# FPGA_IO.net
KiCad netlist of a schematic drawn in Altium Designer
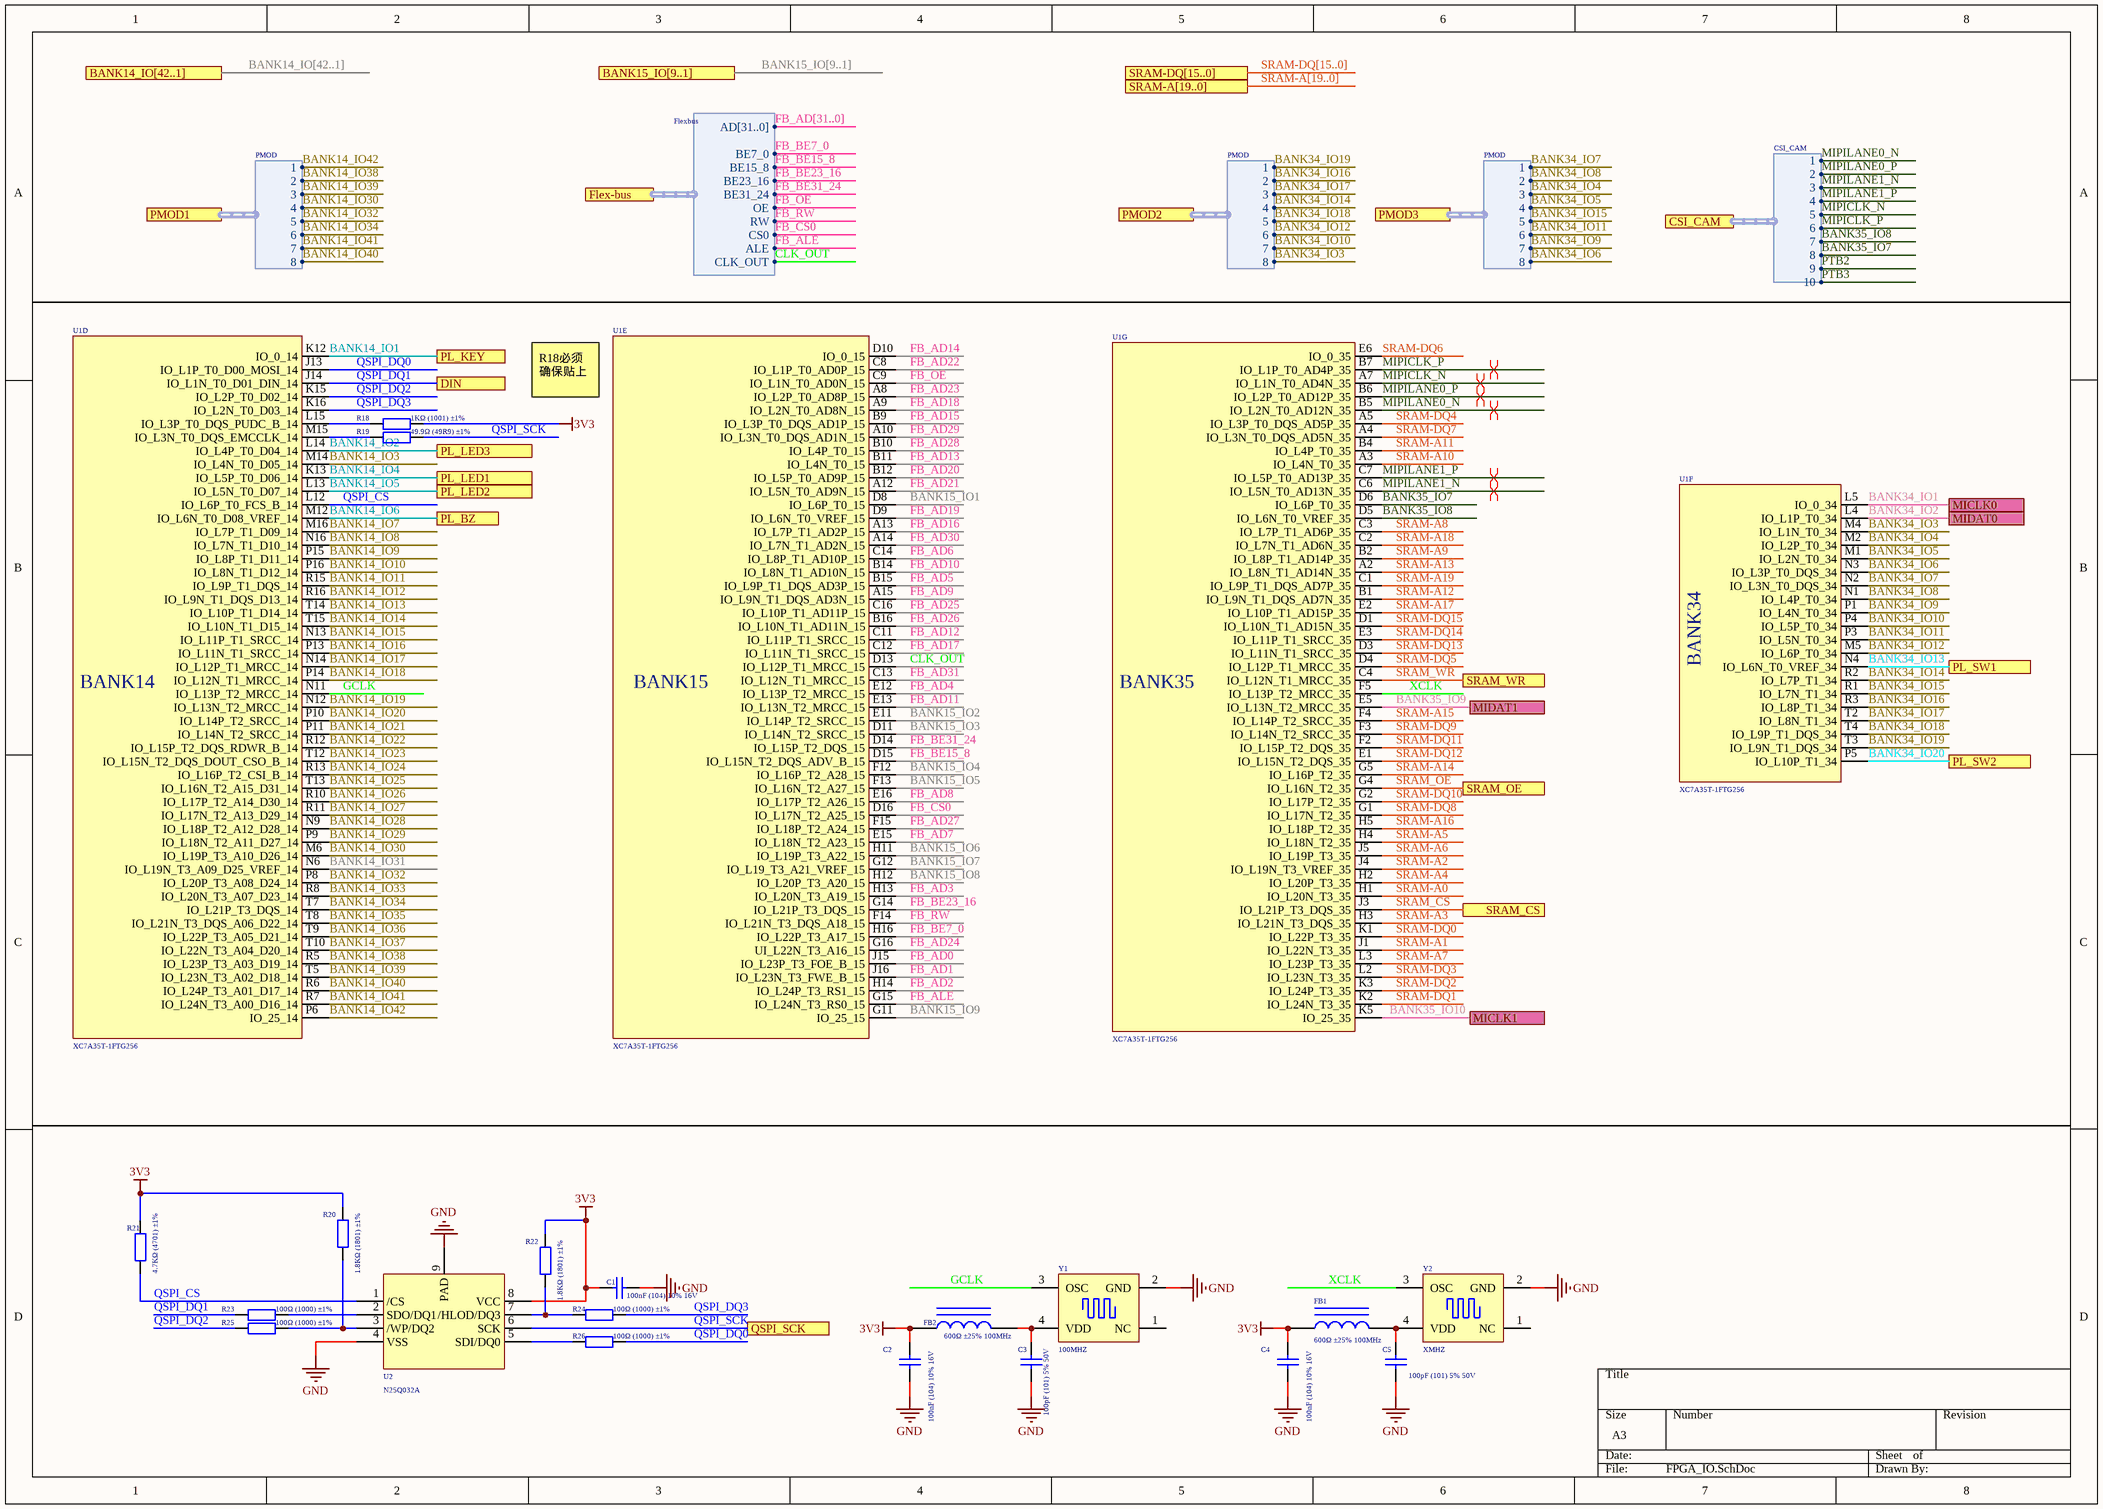
[diagram p0: FPGA_IO.SchDoc]

(export (version "E")
  (design (tool "Eeschema 10.0.6"))
  (components
    (comp (ref "C1")
      (value "100nF (104) 10% 16V")
      (footprint "0402_C")
      (description "贴片电容")
      (libsource (lib "Cap") (part "0402 100nF (104) 10% 16V"))
    )
    (comp (ref "C2")
      (value "100nF (104) 10% 16V")
      (footprint "0402_C")
      (description "贴片电容")
      (libsource (lib "Cap") (part "0402 100nF (104) 10% 16V"))
    )
    (comp (ref "C3")
      (value "100pF (101) 5% 50V")
      (footprint "0402_C")
      (description "贴片电容")
      (libsource (lib "Cap") (part "0402 100pF (101) 5% 50V"))
    )
    (comp (ref "C4")
      (value "100nF (104) 10% 16V")
      (footprint "0402_C")
      (description "贴片电容")
      (libsource (lib "Cap") (part "0402 100nF (104) 10% 16V"))
    )
    (comp (ref "C5")
      (value "100pF (101) 5% 50V")
      (footprint "0402_C")
      (description "贴片电容")
      (libsource (lib "Cap") (part "0402 100pF (101) 5% 50V"))
    )
    (comp (ref "FB1")
      (value "600Ω ±25% 100MHz")
      (footprint "0805_L")
      (description "贴片磁珠")
      (libsource (lib "IUD") (part "0805 600Ω 25% 100MHz"))
    )
    (comp (ref "FB2")
      (value "600Ω ±25% 100MHz")
      (footprint "0805_L")
      (description "贴片磁珠")
      (libsource (lib "IUD") (part "0805 600Ω 25% 100MHz"))
    )
    (comp (ref "R18")
      (value "1KΩ (1001) ±1%")
      (footprint "0402_R")
      (description "贴片电阻")
      (libsource (lib "RES") (part "0402 1KΩ (1001) 1%"))
    )
    (comp (ref "R19")
      (value "49.9Ω (49R9) ±1%")
      (footprint "0402_R")
      (description "贴片电阻")
      (libsource (lib "RES") (part "0402 49.9Ω (49R9) 1%"))
    )
    (comp (ref "R20")
      (value "1.8KΩ (1801) ±1%")
      (footprint "0603_R")
      (description "贴片电阻")
      (libsource (lib "RES") (part "0603 1.8KΩ (1801) 1%"))
    )
    (comp (ref "R21")
      (value "4.7KΩ (4701) ±1%")
      (footprint "0402_R")
      (description "贴片电阻")
      (libsource (lib "RES") (part "0402 4.7KΩ (4701) 1%"))
    )
    (comp (ref "R22")
      (value "1.8KΩ (1801) ±1%")
      (footprint "0603_R")
      (description "贴片电阻")
      (libsource (lib "RES") (part "0603 1.8KΩ (1801) 1%"))
    )
    (comp (ref "R23")
      (value "100Ω (1000) ±1%")
      (footprint "0402_R")
      (description "贴片电阻")
      (libsource (lib "RES") (part "0402 100Ω (1000) 1%"))
    )
    (comp (ref "R24")
      (value "100Ω (1000) ±1%")
      (footprint "0402_R")
      (description "贴片电阻")
      (libsource (lib "RES") (part "0402 100Ω (1000) 1%"))
    )
    (comp (ref "R25")
      (value "100Ω (1000) ±1%")
      (footprint "0402_R")
      (description "贴片电阻")
      (libsource (lib "RES") (part "0402 100Ω (1000) 1%"))
    )
    (comp (ref "R26")
      (value "100Ω (1000) ±1%")
      (footprint "0402_R")
      (description "贴片电阻")
      (libsource (lib "RES") (part "0402 100Ω (1000) 1%"))
    )
    (comp (ref "U1")
      (value "XC7A35T-1FTG256")
      (footprint "BGA100P9X9-81A")
      (libsource (lib "Schlib") (part "XC7A35T-1FTG256"))
    )
    (comp (ref "U2")
      (value "N25Q032A")
      (footprint "QFN127P500X600X100_HS-9N")
      (libsource (lib "2号库") (part "N25Q032A"))
    )
    (comp (ref "Y1") (value "100MHZ") (footprint "XTAL7_3225") (libsource (lib "K60-V4.0") (part "XTAL1")))
    (comp (ref "Y2") (value "XMHZ") (footprint "XTAL7_3225") (libsource (lib "K60-V4.0") (part "XTAL1")))
  )
  (nets
    (net (code "4") (name "/BANK14_IO1") (class "Default")
      (node (ref "U1") (pin "K12") (pinfunction "IO_0_14_K12") (pintype "passive"))
    )
    (net (code "5") (name "/BANK14_IO2") (class "Default")
      (node (ref "U1") (pin "L14") (pinfunction "IO_L4P_T0_D04_14_L14") (pintype "passive"))
    )
    (net (code "6") (name "/BANK14_IO3") (class "Default")
      (node (ref "U1") (pin "M14") (pinfunction "IO_L4N_T0_D05_14_M14") (pintype "passive"))
    )
    (net (code "7") (name "/BANK14_IO4") (class "Default")
      (node (ref "U1") (pin "K13") (pinfunction "IO_L5P_T0_D06_14_K13") (pintype "passive"))
    )
    (net (code "8") (name "/BANK14_IO5") (class "Default")
      (node (ref "U1") (pin "L13") (pinfunction "IO_L5N_T0_D07_14_L13") (pintype "passive"))
    )
    (net (code "9") (name "/BANK14_IO6") (class "Default")
      (node (ref "U1") (pin "M12") (pinfunction "IO_L6N_T0_D08_VREF_14_M12") (pintype "passive"))
    )
    (net (code "10") (name "/BANK14_IO7") (class "Default")
      (node (ref "U1") (pin "M16") (pinfunction "IO_L7P_T1_D09_14_M16") (pintype "passive"))
    )
    (net (code "11") (name "/BANK14_IO8") (class "Default")
      (node (ref "U1") (pin "N16") (pinfunction "IO_L7N_T1_D10_14_N16") (pintype "passive"))
    )
    (net (code "12") (name "/BANK14_IO9") (class "Default")
      (node (ref "U1") (pin "P15") (pinfunction "IO_L8P_T1_D11_14_P15") (pintype "passive"))
    )
    (net (code "13") (name "/BANK14_IO10") (class "Default")
      (node (ref "U1") (pin "P16") (pinfunction "IO_L8N_T1_D12_14_P16") (pintype "passive"))
    )
    (net (code "14") (name "/BANK14_IO11") (class "Default")
      (node (ref "U1") (pin "R15") (pinfunction "IO_L9P_T1_DQS_14_R15") (pintype "passive"))
    )
    (net (code "15") (name "/BANK14_IO12") (class "Default")
      (node (ref "U1") (pin "R16") (pinfunction "IO_L9N_T1_DQS_D13_14_R16") (pintype "passive"))
    )
    (net (code "16") (name "/BANK14_IO13") (class "Default")
      (node (ref "U1") (pin "T14") (pinfunction "IO_L10P_T1_D14_14_T14") (pintype "passive"))
    )
    (net (code "17") (name "/BANK14_IO14") (class "Default")
      (node (ref "U1") (pin "T15") (pinfunction "IO_L10N_T1_D15_14_T15") (pintype "passive"))
    )
    (net (code "18") (name "/BANK14_IO15") (class "Default")
      (node (ref "U1") (pin "N13") (pinfunction "IO_L11P_T1_SRCC_14_N13") (pintype "passive"))
    )
    (net (code "19") (name "/BANK14_IO16") (class "Default")
      (node (ref "U1") (pin "P13") (pinfunction "IO_L11N_T1_SRCC_14_P13") (pintype "passive"))
    )
    (net (code "20") (name "/BANK14_IO17") (class "Default")
      (node (ref "U1") (pin "N14") (pinfunction "IO_L12P_T1_MRCC_14_N14") (pintype "passive"))
    )
    (net (code "21") (name "/BANK14_IO18") (class "Default")
      (node (ref "U1") (pin "P14") (pinfunction "IO_L12N_T1_MRCC_14_P14") (pintype "passive"))
    )
    (net (code "22") (name "/BANK14_IO19") (class "Default")
      (node (ref "U1") (pin "N12") (pinfunction "IO_L13N_T2_MRCC_14_N12") (pintype "passive"))
    )
    (net (code "23") (name "/BANK14_IO20") (class "Default")
      (node (ref "U1") (pin "P10") (pinfunction "IO_L14P_T2_SRCC_14_P10") (pintype "passive"))
    )
    (net (code "24") (name "/BANK14_IO21") (class "Default")
      (node (ref "U1") (pin "P11") (pinfunction "IO_L14N_T2_SRCC_14_P11") (pintype "passive"))
    )
    (net (code "25") (name "/BANK14_IO22") (class "Default")
      (node (ref "U1") (pin "R12") (pinfunction "IO_L15P_T2_DQS_RDWR_B_14_R12") (pintype "passive"))
    )
    (net (code "26") (name "/BANK14_IO23") (class "Default")
      (node (ref "U1") (pin "T12") (pinfunction "IO_L15N_T2_DQS_DOUT_CSO_B_14_T12") (pintype "passive"))
    )
    (net (code "27") (name "/BANK14_IO24") (class "Default")
      (node (ref "U1") (pin "R13") (pinfunction "IO_L16P_T2_CSI_B_14_R13") (pintype "passive"))
    )
    (net (code "28") (name "/BANK14_IO25") (class "Default")
      (node (ref "U1") (pin "T13") (pinfunction "IO_L16N_T2_A15_D31_14_T13") (pintype "passive"))
    )
    (net (code "29") (name "/BANK14_IO26") (class "Default")
      (node (ref "U1") (pin "R10") (pinfunction "IO_L17P_T2_A14_D30_14_R10") (pintype "passive"))
    )
    (net (code "30") (name "/BANK14_IO27") (class "Default")
      (node (ref "U1") (pin "R11") (pinfunction "IO_L17N_T2_A13_D29_14_R11") (pintype "passive"))
    )
    (net (code "31") (name "/BANK14_IO28") (class "Default")
      (node (ref "U1") (pin "N9") (pinfunction "IO_L18P_T2_A12_D28_14_N9") (pintype "passive"))
    )
    (net (code "32") (name "/BANK14_IO29") (class "Default")
      (node (ref "U1") (pin "P9") (pinfunction "IO_L18N_T2_A11_D27_14_P9") (pintype "passive"))
    )
    (net (code "33") (name "/BANK14_IO30") (class "Default")
      (node (ref "U1") (pin "M6") (pinfunction "IO_L19P_T3_A10_D26_14_M6") (pintype "passive"))
    )
    (net (code "34") (name "/BANK14_IO31") (class "Default")
      (node (ref "U1") (pin "N6") (pinfunction "IO_L19N_T3_A09_D25_VREF_14_N6") (pintype "passive"))
    )
    (net (code "35") (name "/BANK14_IO32") (class "Default")
      (node (ref "U1") (pin "P8") (pinfunction "IO_L20P_T3_A08_D24_14_P8") (pintype "passive"))
    )
    (net (code "36") (name "/BANK14_IO33") (class "Default")
      (node (ref "U1") (pin "R8") (pinfunction "IO_L20N_T3_A07_D23_14_R8") (pintype "passive"))
    )
    (net (code "37") (name "/BANK14_IO34") (class "Default")
      (node (ref "U1") (pin "T7") (pinfunction "IO_L21P_T3_DQS_14_T7") (pintype "passive"))
    )
    (net (code "38") (name "/BANK14_IO35") (class "Default")
      (node (ref "U1") (pin "T8") (pinfunction "IO_L21N_T3_DQS_A06_D22_14_T8") (pintype "passive"))
    )
    (net (code "39") (name "/BANK14_IO36") (class "Default")
      (node (ref "U1") (pin "T9") (pinfunction "IO_L22P_T3_A05_D21_14_T9") (pintype "passive"))
    )
    (net (code "40") (name "/BANK14_IO37") (class "Default")
      (node (ref "U1") (pin "T10") (pinfunction "IO_L22N_T3_A04_D20_14_T10") (pintype "passive"))
    )
    (net (code "41") (name "/BANK14_IO38") (class "Default")
      (node (ref "U1") (pin "R5") (pinfunction "IO_L23P_T3_A03_D19_14_R5") (pintype "passive"))
    )
    (net (code "42") (name "/BANK14_IO39") (class "Default")
      (node (ref "U1") (pin "T5") (pinfunction "IO_L23N_T3_A02_D18_14_T5") (pintype "passive"))
    )
    (net (code "43") (name "/BANK14_IO40") (class "Default")
      (node (ref "U1") (pin "R6") (pinfunction "IO_L24P_T3_A01_D17_14_R6") (pintype "passive"))
    )
    (net (code "44") (name "/BANK14_IO41") (class "Default")
      (node (ref "U1") (pin "R7") (pinfunction "IO_L24N_T3_A00_D16_14_R7") (pintype "passive"))
    )
    (net (code "45") (name "/BANK14_IO42") (class "Default")
      (node (ref "U1") (pin "P6") (pinfunction "IO_25_14_P6") (pintype "passive"))
    )
    (net (code "47") (name "/BANK15_IO1") (class "Default")
      (node (ref "U1") (pin "D8") (pinfunction "IO_L6P_T0_15_D8") (pintype "passive"))
    )
    (net (code "48") (name "/BANK15_IO2") (class "Default")
      (node (ref "U1") (pin "E11") (pinfunction "IO_L14P_T2_SRCC_15_E11") (pintype "passive"))
    )
    (net (code "49") (name "/BANK15_IO3") (class "Default")
      (node (ref "U1") (pin "D11") (pinfunction "IO_L14N_T2_SRCC_15_D11") (pintype "passive"))
    )
    (net (code "50") (name "/BANK15_IO4") (class "Default")
      (node (ref "U1") (pin "F12") (pinfunction "IO_L16P_T2_A28_15_F12") (pintype "passive"))
    )
    (net (code "51") (name "/BANK15_IO5") (class "Default")
      (node (ref "U1") (pin "F13") (pinfunction "IO_L16N_T2_A27_15_F13") (pintype "passive"))
    )
    (net (code "52") (name "/BANK15_IO6") (class "Default")
      (node (ref "U1") (pin "H11") (pinfunction "IO_L19P_T3_A22_15_H11") (pintype "passive"))
    )
    (net (code "53") (name "/BANK15_IO7") (class "Default")
      (node (ref "U1") (pin "G12") (pinfunction "IO_L19_T3_A21_VREF_15_G12") (pintype "passive"))
    )
    (net (code "54") (name "/BANK15_IO8") (class "Default")
      (node (ref "U1") (pin "H12") (pinfunction "IO_L20P_T3_A20_15_H12") (pintype "passive"))
    )
    (net (code "55") (name "/BANK15_IO9") (class "Default")
      (node (ref "U1") (pin "G11") (pinfunction "IO_25_15_G11") (pintype "passive"))
    )
    (net (code "57") (name "/BANK34_IO1") (class "Default")
      (node (ref "U1") (pin "L5") (pinfunction "IO_0_34_L5") (pintype "passive"))
    )
    (net (code "58") (name "/BANK34_IO2") (class "Default")
      (node (ref "U1") (pin "L4") (pinfunction "IO_L1P_T0_34_L4") (pintype "passive"))
    )
    (net (code "59") (name "/BANK34_IO3") (class "Default")
      (node (ref "U1") (pin "M4") (pinfunction "IO_L1N_T0_34_M4") (pintype "passive"))
    )
    (net (code "60") (name "/BANK34_IO4") (class "Default")
      (node (ref "U1") (pin "M2") (pinfunction "IO_L2P_T0_34_M2") (pintype "passive"))
    )
    (net (code "61") (name "/BANK34_IO5") (class "Default")
      (node (ref "U1") (pin "M1") (pinfunction "IO_L2N_T0_34_M1") (pintype "passive"))
    )
    (net (code "62") (name "/BANK34_IO6") (class "Default")
      (node (ref "U1") (pin "N3") (pinfunction "IO_L3P_T0_DQS_34_N3") (pintype "passive"))
    )
    (net (code "63") (name "/BANK34_IO7") (class "Default")
      (node (ref "U1") (pin "N2") (pinfunction "IO_L3N_T0_DQS_34_N2") (pintype "passive"))
    )
    (net (code "64") (name "/BANK34_IO8") (class "Default")
      (node (ref "U1") (pin "N1") (pinfunction "IO_L4P_T0_34_N1") (pintype "passive"))
    )
    (net (code "65") (name "/BANK34_IO9") (class "Default")
      (node (ref "U1") (pin "P1") (pinfunction "IO_L4N_T0_34_P1") (pintype "passive"))
    )
    (net (code "66") (name "/BANK34_IO10") (class "Default")
      (node (ref "U1") (pin "P4") (pinfunction "IO_L5P_T0_34_P4") (pintype "passive"))
    )
    (net (code "67") (name "/BANK34_IO11") (class "Default")
      (node (ref "U1") (pin "P3") (pinfunction "IO_L5N_T0_34_P3") (pintype "passive"))
    )
    (net (code "68") (name "/BANK34_IO12") (class "Default")
      (node (ref "U1") (pin "M5") (pinfunction "IO_L6P_T0_34_M5") (pintype "passive"))
    )
    (net (code "69") (name "/BANK34_IO13") (class "Default")
      (node (ref "U1") (pin "N4") (pinfunction "IO_L6N_T0_VREF_34_N4") (pintype "passive"))
    )
    (net (code "70") (name "/BANK34_IO14") (class "Default")
      (node (ref "U1") (pin "R2") (pinfunction "IO_L7P_T1_34_R2") (pintype "passive"))
    )
    (net (code "71") (name "/BANK34_IO15") (class "Default")
      (node (ref "U1") (pin "R1") (pinfunction "IO_L7N_T1_34_R1") (pintype "passive"))
    )
    (net (code "72") (name "/BANK34_IO16") (class "Default")
      (node (ref "U1") (pin "R3") (pinfunction "IO_L8P_T1_34_R3") (pintype "passive"))
    )
    (net (code "73") (name "/BANK34_IO17") (class "Default")
      (node (ref "U1") (pin "T2") (pinfunction "IO_L8N_T1_34_T2") (pintype "passive"))
    )
    (net (code "74") (name "/BANK34_IO18") (class "Default")
      (node (ref "U1") (pin "T4") (pinfunction "IO_L9P_T1_DQS_34_T4") (pintype "passive"))
    )
    (net (code "75") (name "/BANK34_IO19") (class "Default")
      (node (ref "U1") (pin "T3") (pinfunction "IO_L9N_T1_DQS_34_T3") (pintype "passive"))
    )
    (net (code "76") (name "/BANK34_IO20") (class "Default")
      (node (ref "U1") (pin "P5") (pinfunction "IO_L10P_T1_34_P5") (pintype "passive"))
    )
    (net (code "77") (name "/BANK35_IO7") (class "Default")
      (node (ref "U1") (pin "D6") (pinfunction "IO_L6P_T0_35_D6") (pintype "passive"))
    )
    (net (code "78") (name "/BANK35_IO8") (class "Default")
      (node (ref "U1") (pin "D5") (pinfunction "IO_L6N_T0_VREF_35_D5") (pintype "passive"))
    )
    (net (code "79") (name "/BANK35_IO9") (class "Default")
      (node (ref "U1") (pin "E5") (pinfunction "IO_L13N_T2_MRCC_35_E5") (pintype "passive"))
    )
    (net (code "80") (name "/BANK35_IO10") (class "Default")
      (node (ref "U1") (pin "K5") (pinfunction "IO_25_35_K5") (pintype "passive"))
    )
    (net (code "81") (name "/CLK_OUT") (class "Default")
      (node (ref "U1") (pin "D13") (pinfunction "IO_L12P_T1_MRCC_15_D13") (pintype "passive"))
    )
    (net (code "82") (name "/FB_AD0") (class "Default")
      (node (ref "U1") (pin "J15") (pinfunction "IO_L23P_T3_FOE_B_15_J15") (pintype "passive"))
    )
    (net (code "83") (name "/FB_AD1") (class "Default")
      (node (ref "U1") (pin "J16") (pinfunction "IO_L23N_T3_FWE_B_15_J16") (pintype "passive"))
    )
    (net (code "84") (name "/FB_AD2") (class "Default")
      (node (ref "U1") (pin "H14") (pinfunction "IO_L24P_T3_RS1_15_H14") (pintype "passive"))
    )
    (net (code "85") (name "/FB_AD3") (class "Default")
      (node (ref "U1") (pin "H13") (pinfunction "IO_L20N_T3_A19_15_H13") (pintype "passive"))
    )
    (net (code "86") (name "/FB_AD4") (class "Default")
      (node (ref "U1") (pin "E12") (pinfunction "IO_L13P_T2_MRCC_15_E12") (pintype "passive"))
    )
    (net (code "87") (name "/FB_AD5") (class "Default")
      (node (ref "U1") (pin "B15") (pinfunction "IO_L9P_T1_DQS_AD3P_15_B15") (pintype "passive"))
    )
    (net (code "88") (name "/FB_AD6") (class "Default")
      (node (ref "U1") (pin "C14") (pinfunction "IO_L8P_T1_AD10P_15_C14") (pintype "passive"))
    )
    (net (code "89") (name "/FB_AD7") (class "Default")
      (node (ref "U1") (pin "E15") (pinfunction "IO_L18N_T2_A23_15_E15") (pintype "passive"))
    )
    (net (code "90") (name "/FB_AD8") (class "Default")
      (node (ref "U1") (pin "E16") (pinfunction "IO_L17P_T2_A26_15_E16") (pintype "passive"))
    )
    (net (code "91") (name "/FB_AD9") (class "Default")
      (node (ref "U1") (pin "A15") (pinfunction "IO_L9N_T1_DQS_AD3N_15_A15") (pintype "passive"))
    )
    (net (code "92") (name "/FB_AD10") (class "Default")
      (node (ref "U1") (pin "B14") (pinfunction "IO_L8N_T1_AD10N_15_B14") (pintype "passive"))
    )
    (net (code "93") (name "/FB_AD11") (class "Default")
      (node (ref "U1") (pin "E13") (pinfunction "IO_L13N_T2_MRCC_15_E13") (pintype "passive"))
    )
    (net (code "94") (name "/FB_AD12") (class "Default")
      (node (ref "U1") (pin "C11") (pinfunction "IO_L11P_T1_SRCC_15_C11") (pintype "passive"))
    )
    (net (code "95") (name "/FB_AD13") (class "Default")
      (node (ref "U1") (pin "B11") (pinfunction "IO_L4N_T0_15_B11") (pintype "passive"))
    )
    (net (code "96") (name "/FB_AD14") (class "Default")
      (node (ref "U1") (pin "D10") (pinfunction "IO_0_15_D10") (pintype "passive"))
    )
    (net (code "97") (name "/FB_AD15") (class "Default")
      (node (ref "U1") (pin "B9") (pinfunction "IO_L3P_T0_DQS_AD1P_15_B9") (pintype "passive"))
    )
    (net (code "98") (name "/FB_AD16") (class "Default")
      (node (ref "U1") (pin "A13") (pinfunction "IO_L7P_T1_AD2P_15_A13") (pintype "passive"))
    )
    (net (code "99") (name "/FB_AD17") (class "Default")
      (node (ref "U1") (pin "C12") (pinfunction "IO_L11N_T1_SRCC_15_C12") (pintype "passive"))
    )
    (net (code "100") (name "/FB_AD18") (class "Default")
      (node (ref "U1") (pin "A9") (pinfunction "IO_L2N_T0_AD8N_15_A9") (pintype "passive"))
    )
    (net (code "101") (name "/FB_AD19") (class "Default")
      (node (ref "U1") (pin "D9") (pinfunction "IO_L6N_T0_VREF_15_D9") (pintype "passive"))
    )
    (net (code "102") (name "/FB_AD20") (class "Default")
      (node (ref "U1") (pin "B12") (pinfunction "IO_L5P_T0_AD9P_15_B12") (pintype "passive"))
    )
    (net (code "103") (name "/FB_AD21") (class "Default")
      (node (ref "U1") (pin "A12") (pinfunction "IO_L5N_T0_AD9N_15_A12") (pintype "passive"))
    )
    (net (code "104") (name "/FB_AD22") (class "Default")
      (node (ref "U1") (pin "C8") (pinfunction "IO_L1P_T0_AD0P_15_C8") (pintype "passive"))
    )
    (net (code "105") (name "/FB_AD23") (class "Default")
      (node (ref "U1") (pin "A8") (pinfunction "IO_L2P_T0_AD8P_15_A8") (pintype "passive"))
    )
    (net (code "106") (name "/FB_AD24") (class "Default")
      (node (ref "U1") (pin "G16") (pinfunction "UI_L22N_T3_A16_15_G16") (pintype "passive"))
    )
    (net (code "107") (name "/FB_AD25") (class "Default")
      (node (ref "U1") (pin "C16") (pinfunction "IO_L10P_T1_AD11P_15_C16") (pintype "passive"))
    )
    (net (code "108") (name "/FB_AD26") (class "Default")
      (node (ref "U1") (pin "B16") (pinfunction "IO_L10N_T1_AD11N_15_B16") (pintype "passive"))
    )
    (net (code "109") (name "/FB_AD27") (class "Default")
      (node (ref "U1") (pin "F15") (pinfunction "IO_L18P_T2_A24_15_F15") (pintype "passive"))
    )
    (net (code "110") (name "/FB_AD28") (class "Default")
      (node (ref "U1") (pin "B10") (pinfunction "IO_L4P_T0_15_B10") (pintype "passive"))
    )
    (net (code "111") (name "/FB_AD29") (class "Default")
      (node (ref "U1") (pin "A10") (pinfunction "IO_L3N_T0_DQS_AD1N_15_A10") (pintype "passive"))
    )
    (net (code "112") (name "/FB_AD30") (class "Default")
      (node (ref "U1") (pin "A14") (pinfunction "IO_L7N_T1_AD2N_15_A14") (pintype "passive"))
    )
    (net (code "113") (name "/FB_AD31") (class "Default")
      (node (ref "U1") (pin "C13") (pinfunction "IO_L12N_T1_MRCC_15_C13") (pintype "passive"))
    )
    (net (code "115") (name "/FB_ALE") (class "Default")
      (node (ref "U1") (pin "G15") (pinfunction "IO_L24N_T3_RS0_15_G15") (pintype "passive"))
    )
    (net (code "116") (name "/FB_BE7_0") (class "Default")
      (node (ref "U1") (pin "H16") (pinfunction "IO_L22P_T3_A17_15_H16") (pintype "passive"))
    )
    (net (code "117") (name "/FB_BE15_8") (class "Default")
      (node (ref "U1") (pin "D15") (pinfunction "IO_L15N_T2_DQS_ADV_B_15_D15") (pintype "passive"))
    )
    (net (code "118") (name "/FB_BE23_16") (class "Default")
      (node (ref "U1") (pin "G14") (pinfunction "IO_L21P_T3_DQS_15_G14") (pintype "passive"))
    )
    (net (code "119") (name "/FB_BE31_24") (class "Default")
      (node (ref "U1") (pin "D14") (pinfunction "IO_L15P_T2_DQS_15_D14") (pintype "passive"))
    )
    (net (code "120") (name "/FB_CS0") (class "Default")
      (node (ref "U1") (pin "D16") (pinfunction "IO_L17N_T2_A25_15_D16") (pintype "passive"))
    )
    (net (code "121") (name "/FB_OE") (class "Default")
      (node (ref "U1") (pin "C9") (pinfunction "IO_L1N_T0_AD0N_15_C9") (pintype "passive"))
    )
    (net (code "122") (name "/FB_RW") (class "Default")
      (node (ref "U1") (pin "F14") (pinfunction "IO_L21N_T3_DQS_A18_15_F14") (pintype "passive"))
    )
    (net (code "123") (name "/GCLK") (class "Default")
      (node (ref "U1") (pin "N11") (pinfunction "IO_L13P_T2_MRCC_14_N11") (pintype "passive"))
      (node (ref "Y1") (pin "3") (pinfunction "OSC_3") (pintype "passive"))
    )
    (net (code "124") (name "/MIPICLK_N") (class "Default")
      (node (ref "U1") (pin "A7") (pinfunction "IO_L1N_T0_AD4N_35_A7") (pintype "passive"))
    )
    (net (code "125") (name "/MIPICLK_P") (class "Default")
      (node (ref "U1") (pin "B7") (pinfunction "IO_L1P_T0_AD4P_35_B7") (pintype "passive"))
    )
    (net (code "126") (name "/MIPILANE0_N") (class "Default")
      (node (ref "U1") (pin "B5") (pinfunction "IO_L2N_T0_AD12N_35_B5") (pintype "passive"))
    )
    (net (code "127") (name "/MIPILANE0_P") (class "Default")
      (node (ref "U1") (pin "B6") (pinfunction "IO_L2P_T0_AD12P_35_B6") (pintype "passive"))
    )
    (net (code "128") (name "/MIPILANE1_N") (class "Default")
      (node (ref "U1") (pin "C6") (pinfunction "IO_L5N_T0_AD13N_35_C6") (pintype "passive"))
    )
    (net (code "129") (name "/MIPILANE1_P") (class "Default")
      (node (ref "U1") (pin "C7") (pinfunction "IO_L5P_T0_AD13P_35_C7") (pintype "passive"))
    )
    (net (code "132") (name "/QSPI_CS") (class "Default")
      (node (ref "R21") (pin "1") (pinfunction "1_1") (pintype "passive"))
      (node (ref "U1") (pin "L12") (pinfunction "IO_L6P_T0_FCS_B_14_L12") (pintype "passive"))
      (node (ref "U2") (pin "1") (pinfunction "/CS_1") (pintype "passive"))
    )
    (net (code "133") (name "/QSPI_DQ0") (class "Default")
      (node (ref "R26") (pin "2") (pinfunction "2_2") (pintype "passive"))
      (node (ref "U1") (pin "J13") (pinfunction "IO_L1P_T0_D00_MOSI_14_J13") (pintype "passive"))
    )
    (net (code "134") (name "/QSPI_DQ1") (class "Default")
      (node (ref "R23") (pin "1") (pinfunction "1_1") (pintype "passive"))
      (node (ref "U1") (pin "J14") (pinfunction "IO_L1N_T0_D01_DIN_14_J14") (pintype "passive"))
    )
    (net (code "135") (name "/QSPI_DQ2") (class "Default")
      (node (ref "R25") (pin "1") (pinfunction "1_1") (pintype "passive"))
      (node (ref "U1") (pin "K15") (pinfunction "IO_L2P_T0_D02_14_K15") (pintype "passive"))
    )
    (net (code "136") (name "/QSPI_DQ3") (class "Default")
      (node (ref "R24") (pin "2") (pinfunction "2_2") (pintype "passive"))
      (node (ref "U1") (pin "K16") (pinfunction "IO_L2N_T0_D03_14_K16") (pintype "passive"))
    )
    (net (code "137") (name "/QSPI_SCK") (class "Default")
      (node (ref "R19") (pin "2") (pinfunction "2_2") (pintype "passive"))
      (node (ref "U2") (pin "6") (pinfunction "SCK_6") (pintype "passive"))
    )
    (net (code "138") (name "/SRAM-A0") (class "Default")
      (node (ref "U1") (pin "H1") (pinfunction "IO_L20N_T3_35_H1") (pintype "passive"))
    )
    (net (code "139") (name "/SRAM-A1") (class "Default")
      (node (ref "U1") (pin "J1") (pinfunction "IO_L22N_T3_35_J1") (pintype "passive"))
    )
    (net (code "140") (name "/SRAM-A2") (class "Default")
      (node (ref "U1") (pin "J4") (pinfunction "IO_L19N_T3_VREF_35_J4") (pintype "passive"))
    )
    (net (code "141") (name "/SRAM-A3") (class "Default")
      (node (ref "U1") (pin "H3") (pinfunction "IO_L21N_T3_DQS_35_H3") (pintype "passive"))
    )
    (net (code "142") (name "/SRAM-A4") (class "Default")
      (node (ref "U1") (pin "H2") (pinfunction "IO_L20P_T3_35_H2") (pintype "passive"))
    )
    (net (code "143") (name "/SRAM-A5") (class "Default")
      (node (ref "U1") (pin "H4") (pinfunction "IO_L18N_T2_35_H4") (pintype "passive"))
    )
    (net (code "144") (name "/SRAM-A6") (class "Default")
      (node (ref "U1") (pin "J5") (pinfunction "IO_L19P_T3_35_J5") (pintype "passive"))
    )
    (net (code "145") (name "/SRAM-A7") (class "Default")
      (node (ref "U1") (pin "L3") (pinfunction "IO_L23P_T3_35_L3") (pintype "passive"))
    )
    (net (code "146") (name "/SRAM-A8") (class "Default")
      (node (ref "U1") (pin "C3") (pinfunction "IO_L7P_T1_AD6P_35_C3") (pintype "passive"))
    )
    (net (code "147") (name "/SRAM-A9") (class "Default")
      (node (ref "U1") (pin "B2") (pinfunction "IO_L8P_T1_AD14P_35_B2") (pintype "passive"))
    )
    (net (code "148") (name "/SRAM-A10") (class "Default")
      (node (ref "U1") (pin "A3") (pinfunction "IO_L4N_T0_35_A3") (pintype "passive"))
    )
    (net (code "149") (name "/SRAM-A11") (class "Default")
      (node (ref "U1") (pin "B4") (pinfunction "IO_L4P_T0_35_B4") (pintype "passive"))
    )
    (net (code "150") (name "/SRAM-A12") (class "Default")
      (node (ref "U1") (pin "B1") (pinfunction "IO_L9N_T1_DQS_AD7N_35_B1") (pintype "passive"))
    )
    (net (code "151") (name "/SRAM-A13") (class "Default")
      (node (ref "U1") (pin "A2") (pinfunction "IO_L8N_T1_AD14N_35_A2") (pintype "passive"))
    )
    (net (code "152") (name "/SRAM-A14") (class "Default")
      (node (ref "U1") (pin "G5") (pinfunction "IO_L16P_T2_35_G5") (pintype "passive"))
    )
    (net (code "153") (name "/SRAM-A15") (class "Default")
      (node (ref "U1") (pin "F4") (pinfunction "IO_L14P_T2_SRCC_35_F4") (pintype "passive"))
    )
    (net (code "154") (name "/SRAM-A16") (class "Default")
      (node (ref "U1") (pin "H5") (pinfunction "IO_L18P_T2_35_H5") (pintype "passive"))
    )
    (net (code "155") (name "/SRAM-A17") (class "Default")
      (node (ref "U1") (pin "E2") (pinfunction "IO_L10P_T1_AD15P_35_E2") (pintype "passive"))
    )
    (net (code "156") (name "/SRAM-A18") (class "Default")
      (node (ref "U1") (pin "C2") (pinfunction "IO_L7N_T1_AD6N_35_C2") (pintype "passive"))
    )
    (net (code "157") (name "/SRAM-A19") (class "Default")
      (node (ref "U1") (pin "C1") (pinfunction "IO_L9P_T1_DQS_AD7P_35_C1") (pintype "passive"))
    )
    (net (code "159") (name "/SRAM-DQ0") (class "Default")
      (node (ref "U1") (pin "K1") (pinfunction "IO_L22P_T3_35_K1") (pintype "passive"))
    )
    (net (code "160") (name "/SRAM-DQ1") (class "Default")
      (node (ref "U1") (pin "K2") (pinfunction "IO_L24N_T3_35_K2") (pintype "passive"))
    )
    (net (code "161") (name "/SRAM-DQ2") (class "Default")
      (node (ref "U1") (pin "K3") (pinfunction "IO_L24P_T3_35_K3") (pintype "passive"))
    )
    (net (code "162") (name "/SRAM-DQ3") (class "Default")
      (node (ref "U1") (pin "L2") (pinfunction "IO_L23N_T3_35_L2") (pintype "passive"))
    )
    (net (code "163") (name "/SRAM-DQ4") (class "Default")
      (node (ref "U1") (pin "A5") (pinfunction "IO_L3P_T0_DQS_AD5P_35_A5") (pintype "passive"))
    )
    (net (code "164") (name "/SRAM-DQ5") (class "Default")
      (node (ref "U1") (pin "D4") (pinfunction "IO_L12P_T1_MRCC_35_D4") (pintype "passive"))
    )
    (net (code "165") (name "/SRAM-DQ6") (class "Default")
      (node (ref "U1") (pin "E6") (pinfunction "IO_0_35_E6") (pintype "passive"))
    )
    (net (code "166") (name "/SRAM-DQ7") (class "Default")
      (node (ref "U1") (pin "A4") (pinfunction "IO_L3N_T0_DQS_AD5N_35_A4") (pintype "passive"))
    )
    (net (code "167") (name "/SRAM-DQ8") (class "Default")
      (node (ref "U1") (pin "G1") (pinfunction "IO_L17N_T2_35_G1") (pintype "passive"))
    )
    (net (code "168") (name "/SRAM-DQ9") (class "Default")
      (node (ref "U1") (pin "F3") (pinfunction "IO_L14N_T2_SRCC_35_F3") (pintype "passive"))
    )
    (net (code "169") (name "/SRAM-DQ10") (class "Default")
      (node (ref "U1") (pin "G2") (pinfunction "IO_L17P_T2_35_G2") (pintype "passive"))
    )
    (net (code "170") (name "/SRAM-DQ11") (class "Default")
      (node (ref "U1") (pin "F2") (pinfunction "IO_L15P_T2_DQS_35_F2") (pintype "passive"))
    )
    (net (code "171") (name "/SRAM-DQ12") (class "Default")
      (node (ref "U1") (pin "E1") (pinfunction "IO_L15N_T2_DQS_35_E1") (pintype "passive"))
    )
    (net (code "172") (name "/SRAM-DQ13") (class "Default")
      (node (ref "U1") (pin "D3") (pinfunction "IO_L11N_T1_SRCC_35_D3") (pintype "passive"))
    )
    (net (code "173") (name "/SRAM-DQ14") (class "Default")
      (node (ref "U1") (pin "E3") (pinfunction "IO_L11P_T1_SRCC_35_E3") (pintype "passive"))
    )
    (net (code "174") (name "/SRAM-DQ15") (class "Default")
      (node (ref "U1") (pin "D1") (pinfunction "IO_L10N_T1_AD15N_35_D1") (pintype "passive"))
    )
    (net (code "176") (name "/SRAM_CS") (class "Default")
      (node (ref "U1") (pin "J3") (pinfunction "IO_L21P_T3_DQS_35_J3") (pintype "passive"))
    )
    (net (code "177") (name "/SRAM_OE") (class "Default")
      (node (ref "U1") (pin "G4") (pinfunction "IO_L16N_T2_35_G4") (pintype "passive"))
    )
    (net (code "178") (name "/SRAM_WR") (class "Default")
      (node (ref "U1") (pin "C4") (pinfunction "IO_L12N_T1_MRCC_35_C4") (pintype "passive"))
    )
    (net (code "179") (name "/XCLK") (class "Default")
      (node (ref "U1") (pin "F5") (pinfunction "IO_L13P_T2_MRCC_35_F5") (pintype "passive"))
      (node (ref "Y2") (pin "3") (pinfunction "OSC_3") (pintype "passive"))
    )
    (net (code "183") (name "3V3") (class "Default")
      (node (ref "C1") (pin "1") (pinfunction "1_1") (pintype "passive"))
      (node (ref "C2") (pin "2") (pinfunction "2_2") (pintype "passive"))
      (node (ref "C4") (pin "2") (pinfunction "2_2") (pintype "passive"))
      (node (ref "FB1") (pin "1") (pinfunction "1_1") (pintype "passive"))
      (node (ref "FB2") (pin "1") (pinfunction "1_1") (pintype "passive"))
      (node (ref "R18") (pin "2") (pinfunction "2_2") (pintype "passive"))
      (node (ref "R20") (pin "2") (pinfunction "2_2") (pintype "passive"))
      (node (ref "R21") (pin "2") (pinfunction "2_2") (pintype "passive"))
      (node (ref "R22") (pin "2") (pinfunction "2_2") (pintype "passive"))
      (node (ref "U2") (pin "8") (pinfunction "VCC_8") (pintype "passive"))
    )
    (net (code "184") (name "GND") (class "Default")
      (node (ref "C1") (pin "2") (pinfunction "2_2") (pintype "passive"))
      (node (ref "C2") (pin "1") (pinfunction "1_1") (pintype "passive"))
      (node (ref "C3") (pin "1") (pinfunction "1_1") (pintype "passive"))
      (node (ref "C4") (pin "1") (pinfunction "1_1") (pintype "passive"))
      (node (ref "C5") (pin "1") (pinfunction "1_1") (pintype "passive"))
      (node (ref "U2") (pin "4") (pinfunction "VSS_4") (pintype "passive"))
      (node (ref "U2") (pin "9") (pinfunction "PAD_9") (pintype "passive"))
      (node (ref "Y1") (pin "2") (pinfunction "GND_2") (pintype "passive"))
      (node (ref "Y2") (pin "2") (pinfunction "GND_2") (pintype "passive"))
    )
    (net (code "185") (name "Net-(U1D-IO_L3N_T0_DQS_EMCCLK_14)") (class "Default")
      (node (ref "R19") (pin "1") (pinfunction "1_1") (pintype "passive"))
      (node (ref "U1") (pin "M15") (pinfunction "IO_L3N_T0_DQS_EMCCLK_14_M15") (pintype "passive"))
    )
    (net (code "186") (name "Net-(U1D-IO_L3P_T0_DQS_PUDC_B_14)") (class "Default")
      (node (ref "R18") (pin "1") (pinfunction "1_1") (pintype "passive"))
      (node (ref "U1") (pin "L15") (pinfunction "IO_L3P_T0_DQS_PUDC_B_14_L15") (pintype "passive"))
    )
    (net (code "187") (name "Net-(U2-SDI{slash}DQ0)") (class "Default")
      (node (ref "R26") (pin "1") (pinfunction "1_1") (pintype "passive"))
      (node (ref "U2") (pin "5") (pinfunction "SDI/DQ0_5") (pintype "passive"))
    )
    (net (code "188") (name "Net-(U2-SDO{slash}DQ1)") (class "Default")
      (node (ref "R23") (pin "2") (pinfunction "2_2") (pintype "passive"))
      (node (ref "U2") (pin "2") (pinfunction "SDO/DQ1_2") (pintype "passive"))
    )
    (net (code "189") (name "Net-(U2-{slash}HLOD{slash}DQ3)") (class "Default")
      (node (ref "R22") (pin "1") (pinfunction "1_1") (pintype "passive"))
      (node (ref "R24") (pin "1") (pinfunction "1_1") (pintype "passive"))
      (node (ref "U2") (pin "7") (pinfunction "/HLOD/DQ3_7") (pintype "passive"))
    )
    (net (code "190") (name "Net-(U2-{slash}WP{slash}DQ2)") (class "Default")
      (node (ref "R20") (pin "1") (pinfunction "1_1") (pintype "passive"))
      (node (ref "R25") (pin "2") (pinfunction "2_2") (pintype "passive"))
      (node (ref "U2") (pin "3") (pinfunction "/WP/DQ2_3") (pintype "passive"))
    )
    (net (code "191") (name "Net-(Y1-VDD)") (class "Default")
      (node (ref "C3") (pin "2") (pinfunction "2_2") (pintype "passive"))
      (node (ref "FB2") (pin "2") (pinfunction "2_2") (pintype "passive"))
      (node (ref "Y1") (pin "4") (pinfunction "VDD_4") (pintype "passive"))
    )
    (net (code "192") (name "Net-(Y2-VDD)") (class "Default")
      (node (ref "C5") (pin "2") (pinfunction "2_2") (pintype "passive"))
      (node (ref "FB1") (pin "2") (pinfunction "2_2") (pintype "passive"))
      (node (ref "Y2") (pin "4") (pinfunction "VDD_4") (pintype "passive"))
    )
    (net (code "193") (name "unconnected-(Y1-NC-Pad1)") (class "Default")
      (node (ref "Y1") (pin "1") (pinfunction "NC_1") (pintype "passive"))
    )
    (net (code "194") (name "unconnected-(Y2-NC-Pad1)") (class "Default")
      (node (ref "Y2") (pin "1") (pinfunction "NC_1") (pintype "passive"))
    )
  )
)
